# Power_Management.net
KiCad netlist of a schematic drawn in Altium Designer
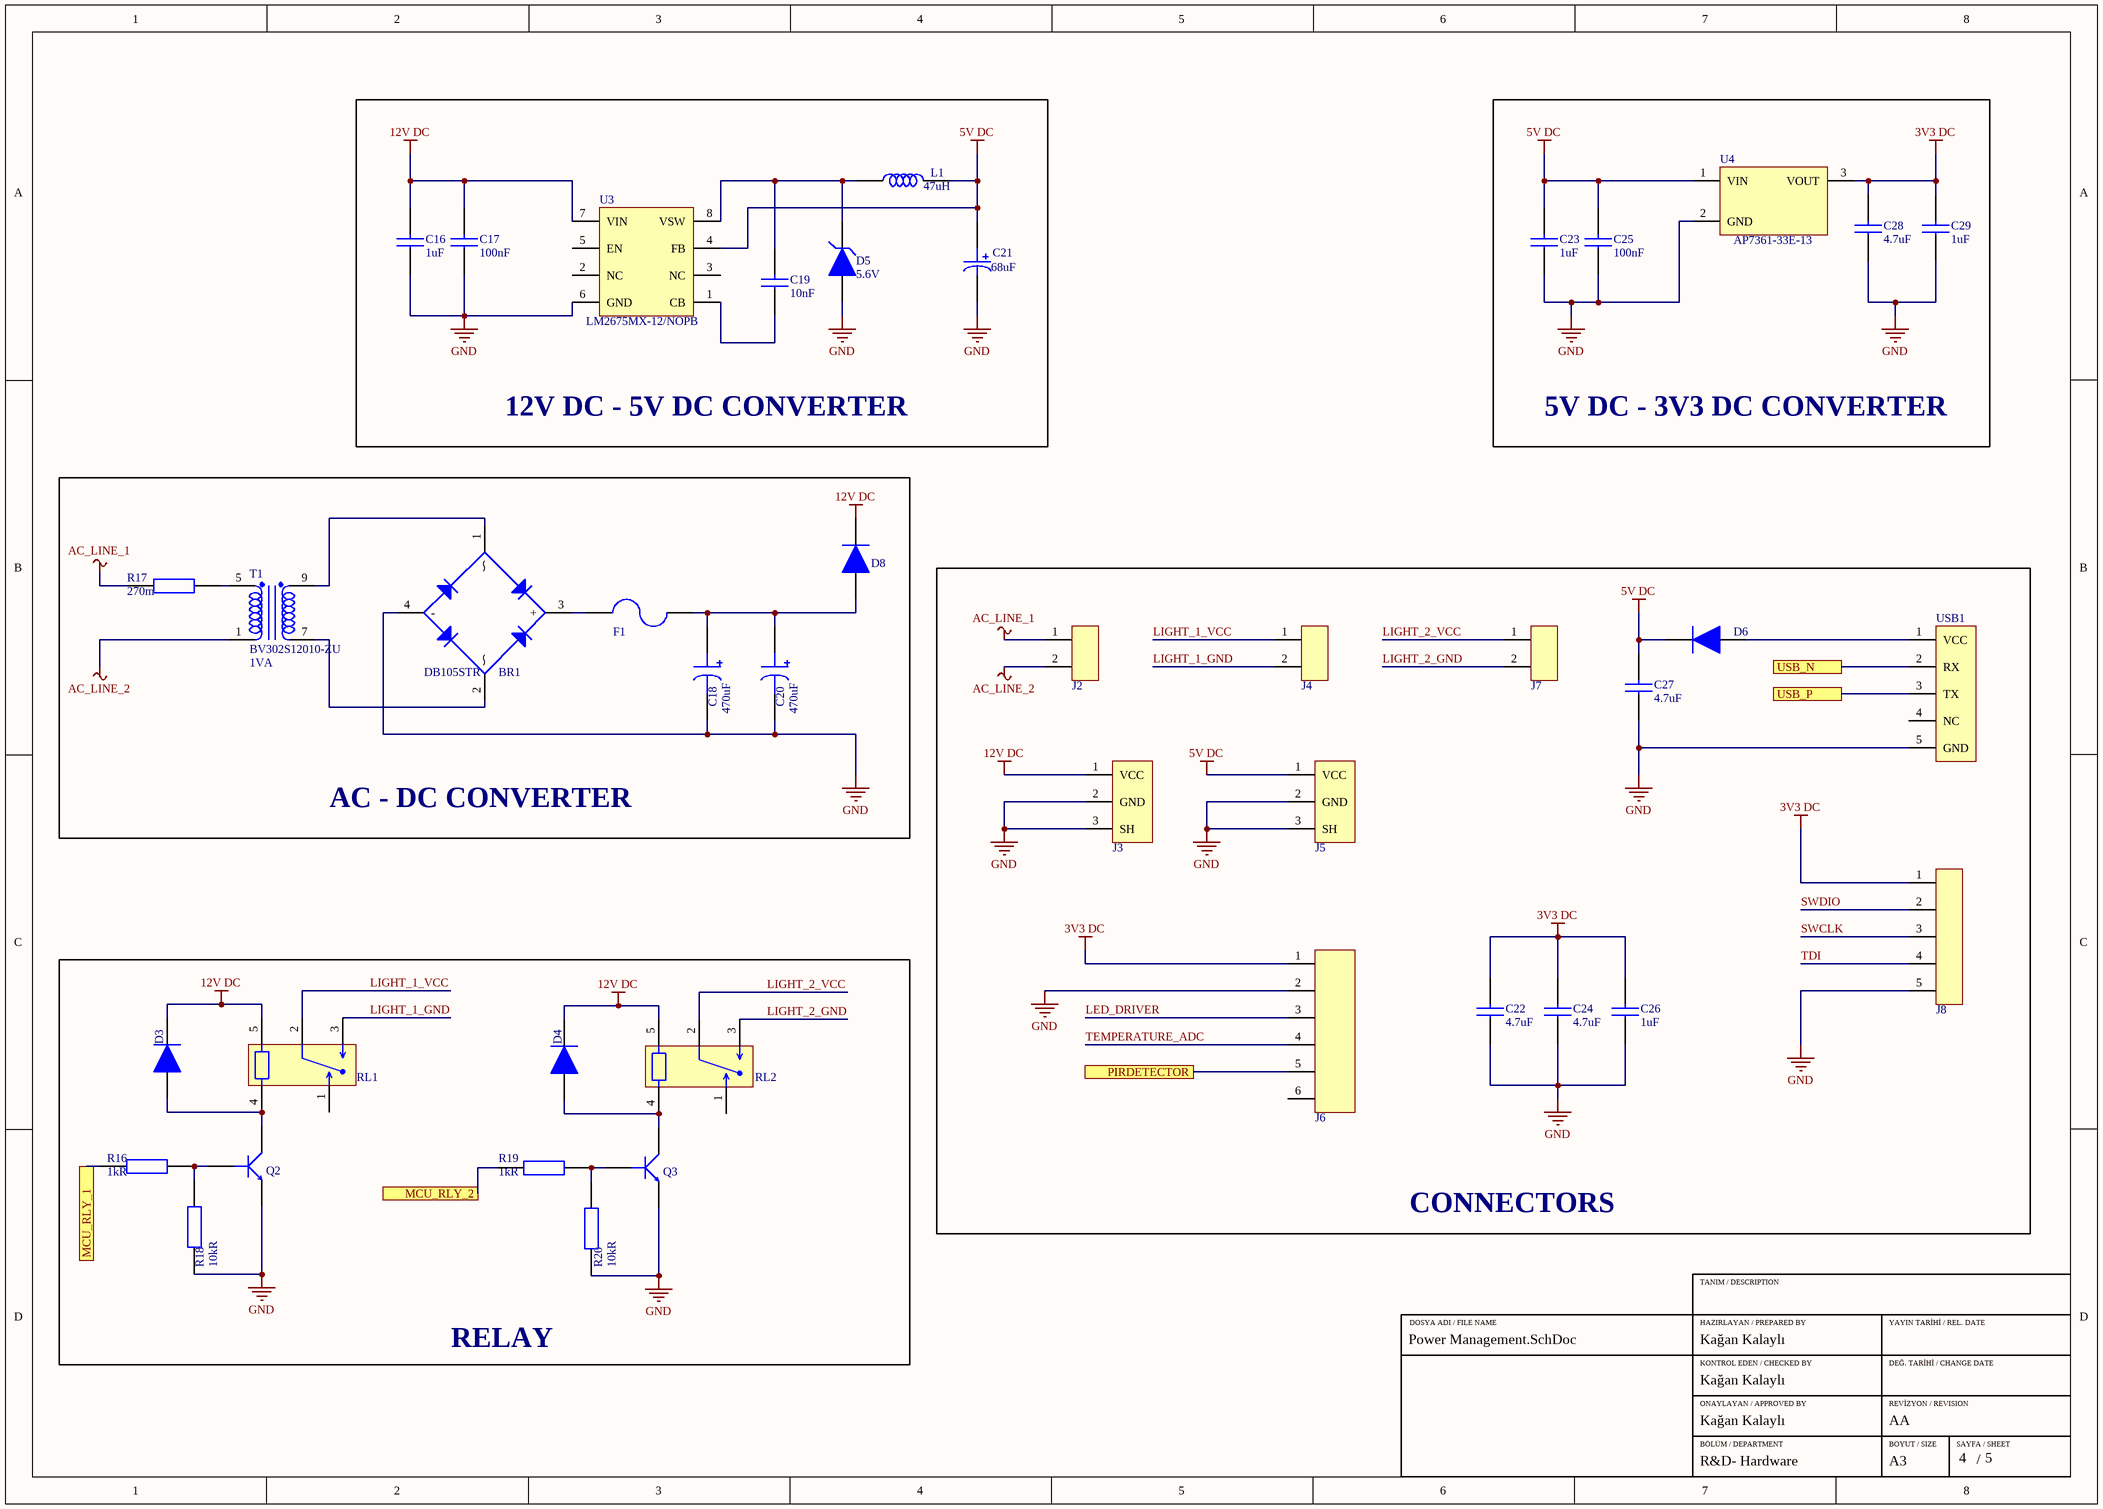
[diagram p0: Power Management.SchDoc]

(export (version "E")
  (design (tool "Eeschema 10.0.6"))
  (components
    (comp (ref "BR1")
      (value "DB105STR")
      (footprint "DB105STR")
      (description "Bridge Rect 1PHASE 600V 1A Db-s")
      (fields
        (field (name "MANUFACTURER") "Sangdest Microelectronics")
        (field (name "MANUFACTURER PART NUMBER") "DB105STR")
        (field (name "DESIGNED BY") "Kağan")
      )
      (libsource (lib "Udemy_Library") (part "DB105STR"))
    )
    (comp (ref "C16")
      (value "CL21B105KBFNNNE")
      (footprint "CAP_0805")
      (description "CAP CER 1uF %10 0805")
      (fields
        (field (name "MANUFACTURER") "Samsung")
        (field (name "TOLERANCE") "10%")
        (field (name "CAPACITANCE") "1uF")
        (field (name "DESIGNED BY") "Kağan")
      )
      (libsource (lib "Udemy_Library") (part "CAP CER 1uF 0805"))
    )
    (comp (ref "C17")
      (value "CL21B104KBCNNNC")
      (footprint "CAP_0805")
      (description "CAP CER 100nF %10 0805")
      (fields
        (field (name "MANUFACTURER") "Samsung")
        (field (name "TOLERANCE") "10%")
        (field (name "CAPACITANCE") "100nF")
        (field (name "DESIGNED BY") "Kağan")
      )
      (libsource (lib "Udemy_Library") (part "CAP CER 100nF 0805"))
    )
    (comp (ref "C18")
      (value "CAP ESH477M050AH4AA")
      (footprint "CAP_RADIAL_D10_P5 - duplicate")
      (description "Cap, 470UF, 50V, Alu Elec, Radial")
      (fields
        (field (name "MANUFACTURER") "KEMET")
        (field (name "MANUFACTURER PART NUMBER") "ESH477M050AH4AA")
        (field (name "CAPACITANCE") "470uF")
        (field (name "DESIGNED BY") "Kağan")
      )
      (libsource (lib "Udemy_Library") (part "CAP ESH477M050AH4AA"))
    )
    (comp (ref "C19")
      (value "0603B103K160CT")
      (footprint "CAP_0603")
      (description "CAP CER 10nF %10 0603")
      (fields
        (field (name "MANUFACTURER") "Walsin Technologies")
        (field (name "TOLERANCE") "10%")
        (field (name "CAPACITANCE") "10nF")
        (field (name "DESIGNED BY") "Kağan")
      )
      (libsource (lib "Udemy_Library") (part "CAP CER 10nF 0603"))
    )
    (comp (ref "C20")
      (value "CAP ESH477M050AH4AA")
      (footprint "CAP_RADIAL_D10_P5 - duplicate")
      (description "Cap, 470UF, 50V, Alu Elec, Radial")
      (fields
        (field (name "MANUFACTURER") "KEMET")
        (field (name "MANUFACTURER PART NUMBER") "ESH477M050AH4AA")
        (field (name "CAPACITANCE") "470uF")
        (field (name "DESIGNED BY") "Kağan")
      )
      (libsource (lib "Udemy_Library") (part "CAP ESH477M050AH4AA"))
    )
    (comp (ref "C21")
      (value "EEV686M035A9HAA")
      (footprint "CAP_EEVseries")
      (description "Cap Aluminum Lytic 68uF 35V 20% (6.3 X 7.7mm) SMD 280mA 2000h 105C T/R")
      (fields
        (field (name "MANUFACTURER") "KEMET")
        (field (name "TOLERANCE") "20%")
        (field (name "CAPACITANCE") "68uF")
        (field (name "DESIGNED BY") "Kağan")
      )
      (libsource (lib "Udemy_Library") (part "CAP ALU 68uF"))
    )
    (comp (ref "C22")
      (value "CL21A475KAQNNNE")
      (footprint "CAP_0805")
      (description "CAP CER 4.7uF %10 0805")
      (fields
        (field (name "MANUFACTURER") "Samsung")
        (field (name "TOLERANCE") "10%")
        (field (name "CAPACITANCE") "4.7uF")
        (field (name "DESIGNED BY") "Kağan")
      )
      (libsource (lib "Udemy_Library") (part "CAP CER 4.7uF 0805"))
    )
    (comp (ref "C23")
      (value "CL21B105KBFNNNE")
      (footprint "CAP_0805")
      (description "CAP CER 1uF %10 0805")
      (fields
        (field (name "MANUFACTURER") "Samsung")
        (field (name "TOLERANCE") "10%")
        (field (name "CAPACITANCE") "1uF")
        (field (name "DESIGNED BY") "Kağan")
      )
      (libsource (lib "Udemy_Library") (part "CAP CER 1uF 0805"))
    )
    (comp (ref "C24")
      (value "CL21A475KAQNNNE")
      (footprint "CAP_0805")
      (description "CAP CER 4.7uF %10 0805")
      (fields
        (field (name "MANUFACTURER") "Samsung")
        (field (name "TOLERANCE") "10%")
        (field (name "CAPACITANCE") "4.7uF")
        (field (name "DESIGNED BY") "Kağan")
      )
      (libsource (lib "Udemy_Library") (part "CAP CER 4.7uF 0805"))
    )
    (comp (ref "C25")
      (value "C0603C104K5RACTU")
      (footprint "CAP_0603")
      (description "CAP CER 100nF %10 0603 SMD")
      (fields
        (field (name "MANUFACTURER") "KEMET")
        (field (name "TOLERANCE") "10%")
        (field (name "CAPACITANCE") "100nF")
        (field (name "DESIGNED BY") "Kağan")
      )
      (libsource (lib "Udemy_Library") (part "CAP CER 100nF 0603_1"))
    )
    (comp (ref "C26")
      (value "CL21B105KBFNNNE")
      (footprint "CAP_0805")
      (description "CAP CER 1uF %10 0805")
      (fields
        (field (name "MANUFACTURER") "Samsung")
        (field (name "TOLERANCE") "10%")
        (field (name "CAPACITANCE") "1uF")
        (field (name "DESIGNED BY") "Kağan")
      )
      (libsource (lib "Udemy_Library") (part "CAP CER 1uF 0805"))
    )
    (comp (ref "C27")
      (value "CL21A475KAQNNNE")
      (footprint "CAP_0805")
      (description "CAP CER 4.7uF %10 0805")
      (fields
        (field (name "MANUFACTURER") "Samsung")
        (field (name "TOLERANCE") "10%")
        (field (name "CAPACITANCE") "4.7uF")
        (field (name "DESIGNED BY") "Kağan")
      )
      (libsource (lib "Udemy_Library") (part "CAP CER 4.7uF 0805"))
    )
    (comp (ref "C28")
      (value "CL21A475KAQNNNE")
      (footprint "CAP_0805")
      (description "CAP CER 4.7uF %10 0805")
      (fields
        (field (name "MANUFACTURER") "Samsung")
        (field (name "TOLERANCE") "10%")
        (field (name "CAPACITANCE") "4.7uF")
        (field (name "DESIGNED BY") "Kağan")
      )
      (libsource (lib "Udemy_Library") (part "CAP CER 4.7uF 0805"))
    )
    (comp (ref "C29")
      (value "CL21B105KBFNNNE")
      (footprint "CAP_0805")
      (description "CAP CER 1uF %10 0805")
      (fields
        (field (name "MANUFACTURER") "Samsung")
        (field (name "TOLERANCE") "10%")
        (field (name "CAPACITANCE") "1uF")
        (field (name "DESIGNED BY") "Kağan")
      )
      (libsource (lib "Udemy_Library") (part "CAP CER 1uF 0805"))
    )
    (comp (ref "D3")
      (value "1N4148WS")
      (footprint "SOD323F")
      (description "Diode, Single, 75 V, 150 mA, 1 V, 4 ns")
      (fields
        (field (name "MANUFACTURER") "ON Semiconductor / Fairchild")
        (field (name "DESIGNED BY") "Kağan")
      )
      (libsource (lib "Udemy_Library") (part "1N4148WS"))
    )
    (comp (ref "D4")
      (value "1N4148WS")
      (footprint "SOD323F")
      (description "Diode, Single, 75 V, 150 mA, 1 V, 4 ns")
      (fields
        (field (name "MANUFACTURER") "ON Semiconductor / Fairchild")
        (field (name "DESIGNED BY") "Kağan")
      )
      (libsource (lib "Udemy_Library") (part "1N4148WS"))
    )
    (comp (ref "D5")
      (value "1SMB5919BT3G")
      (footprint "SMB")
      (description "Diode Zener Single 5.6V 5% 3W 2-Pin SMB T/R")
      (fields
        (field (name "MANUFACTURER") "ON Semiconductor")
        (field (name "TOLERANCE") "5%")
        (field (name "WORKING VOLTAGE") "5.6V")
        (field (name "DESIGNED BY") "Kağan")
      )
      (libsource (lib "Udemy_Library") (part "1SMB5919BT3G"))
    )
    (comp (ref "D6")
      (value "1N4148WS")
      (footprint "SOD323F")
      (description "Diode, Single, 75 V, 150 mA, 1 V, 4 ns")
      (fields
        (field (name "MANUFACTURER") "ON Semiconductor / Fairchild")
        (field (name "DESIGNED BY") "Kağan")
      )
      (libsource (lib "Udemy_Library") (part "1N4148WS"))
    )
    (comp (ref "D8")
      (value "1N4148WS")
      (footprint "SOD323F")
      (description "Diode, Single, 75 V, 150 mA, 1 V, 4 ns")
      (fields
        (field (name "MANUFACTURER") "ON Semiconductor / Fairchild")
        (field (name "DESIGNED BY") "Kağan")
      )
      (libsource (lib "Udemy_Library") (part "1N4148WS"))
    )
    (comp (ref "F1")
      (value "3413.0216.22")
      (footprint "FUSE 3413.0216.22")
      (description "Fuse Chip Fast Acting 1A 32V SMD Solder Pad 1206 Glass T/R VDE/cULus")
      (fields (field (name "MANUFACTURER") "Schurter") (field (name "DESIGNED BY") "Kağan"))
      (libsource (lib "Udemy_Library") (part "FUSE 3413.0216.22"))
    )
    (comp (ref "J2")
      (value "TBP01R1-508-02BE")
      (footprint "TBP01R1-508")
      (description "Conn Shrouded Header HDR 2 POS 5.08mm Solder RA Side Entry Thru-Hole Bag")
      (fields (field (name "MANUFACTURER") "CUI") (field (name "DESIGNED BY") "Kağan"))
      (libsource (lib "Udemy_Library") (part "TBP01R1-508-02BE"))
    )
    (comp (ref "J3")
      (value "PJ-037AH-SMT-TR")
      (footprint "JACK")
      (description "DC Power Connectors Power Jacks")
      (fields (field (name "MANUFACTURER") "CUI") (field (name "DESIGNED BY") "Kağan"))
      (libsource (lib "Udemy_Library") (part "PJ-037AH-SMT-TR"))
    )
    (comp (ref "J4")
      (value "TBP01R1-508-02BE")
      (footprint "TBP01R1-508")
      (description "Conn Shrouded Header HDR 2 POS 5.08mm Solder RA Side Entry Thru-Hole Bag")
      (fields (field (name "MANUFACTURER") "CUI") (field (name "DESIGNED BY") "Kağan"))
      (libsource (lib "Udemy_Library") (part "TBP01R1-508-02BE"))
    )
    (comp (ref "J5")
      (value "PJ-037AH-SMT-TR")
      (footprint "JACK")
      (description "DC Power Connectors Power Jacks")
      (fields (field (name "MANUFACTURER") "CUI") (field (name "DESIGNED BY") "Kağan"))
      (libsource (lib "Udemy_Library") (part "PJ-037AH-SMT-TR"))
    )
    (comp (ref "J6")
      (value "64800611622")
      (footprint "64800611622")
      (description "1.50mm 6PIN Connector")
      (fields (field (name "MANUFACTURER") "Wurth Electronics") (field (name "DESIGNED BY") "Kağan"))
      (libsource (lib "Udemy_Library") (part "64800611622_conn_6pin"))
    )
    (comp (ref "J7")
      (value "TBP01R1-508-02BE")
      (footprint "TBP01R1-508")
      (description "Conn Shrouded Header HDR 2 POS 5.08mm Solder RA Side Entry Thru-Hole Bag")
      (fields (field (name "MANUFACTURER") "CUI") (field (name "DESIGNED BY") "Kağan"))
      (libsource (lib "Udemy_Library") (part "TBP01R1-508-02BE"))
    )
    (comp (ref "J8")
      (value "SMH-105-02-L-S")
      (footprint "PINHEADER1X5_RA")
      (description ".100 C.L. HORIZONTAL SMT SOCKET")
      (fields (field (name "MANUFACTURER") "Samtec") (field (name "DESIGNED BY") "Kağan"))
      (libsource (lib "Udemy_Library") (part "SMH-105-02-L-S"))
    )
    (comp (ref "L1")
      (value "78438335470")
      (footprint "IND_1212")
      (description "FIXED IND 47UH 390MA 2.3 OHM SMD")
      (fields
        (field (name "MANUFACTURER") "Wurth Electronics")
        (field (name "TOLERANCE") "30%")
        (field (name "INDUCTANCE") "47uH")
        (field (name "DESIGNED BY") "Kağan")
      )
      (libsource (lib "Udemy_Library") (part "IND 47uH"))
    )
    (comp (ref "Q2")
      (value "MMBT3904-7-F")
      (footprint "SOT-23F")
      (description "Transistor General Purpose BJT NPN 40 Volt 0.2A Automotive 3-Pin SOT-23")
      (fields (field (name "MANUFACTURER") "Diodes Zetex") (field (name "DESIGNED BY") "Kağan"))
      (libsource (lib "Udemy_Library") (part "MMBT3904-7-F"))
    )
    (comp (ref "Q3")
      (value "MMBT3904-7-F")
      (footprint "SOT-23F")
      (description "Transistor General Purpose BJT NPN 40 Volt 0.2A Automotive 3-Pin SOT-23")
      (fields (field (name "MANUFACTURER") "Diodes Zetex") (field (name "DESIGNED BY") "Kağan"))
      (libsource (lib "Udemy_Library") (part "MMBT3904-7-F"))
    )
    (comp (ref "R16")
      (value "RC0603FR-0710KL")
      (footprint "RES_0603")
      (description "RES 1K %1 OHM 0603 SMD")
      (fields
        (field (name "MANUFACTURER") "Yageo")
        (field (name "MANUFACTURER PART NUMBER") "RC0603JR-071KL")
        (field (name "RESISTANCE") "1kR")
        (field (name "DESIGNED BY") "Kağan")
      )
      (libsource (lib "Udemy_Library") (part "RES 1K OHM 0603"))
    )
    (comp (ref "R17")
      (value "5WD27")
      (footprint "RES_AXIAL_W")
      (description "Resistor 5 Watt Cermet Wirewound Flameproof .27 Ohm 5% Axial Lead")
      (fields
        (field (name "MANUFACTURER") "NTE Electronics")
        (field (name "TOLERANCE") "5%")
        (field (name "RESISTANCE") "270m")
        (field (name "DESIGNED BY") "Kağan")
      )
      (libsource (lib "Udemy_Library") (part "5WD27_1"))
    )
    (comp (ref "R18")
      (value "RC0603FR-0710KL")
      (footprint "RES_0603")
      (description "RES 10K %1 OHM 0603 SMD")
      (fields
        (field (name "MANUFACTURER") "Yageo")
        (field (name "TOLERANCE") "1%")
        (field (name "RESISTANCE") "10kR")
        (field (name "DESIGNED BY") "Kağan")
      )
      (libsource (lib "Udemy_Library") (part "RES 10K OHM 0603"))
    )
    (comp (ref "R19")
      (value "RC0603FR-0710KL")
      (footprint "RES_0603")
      (description "RES 1K %1 OHM 0603 SMD")
      (fields
        (field (name "MANUFACTURER") "Yageo")
        (field (name "MANUFACTURER PART NUMBER") "RC0603JR-071KL")
        (field (name "RESISTANCE") "1kR")
        (field (name "DESIGNED BY") "Kağan")
      )
      (libsource (lib "Udemy_Library") (part "RES 1K OHM 0603"))
    )
    (comp (ref "R20")
      (value "RC0603FR-0710KL")
      (footprint "RES_0603")
      (description "RES 10K %1 OHM 0603 SMD")
      (fields
        (field (name "MANUFACTURER") "Yageo")
        (field (name "TOLERANCE") "1%")
        (field (name "RESISTANCE") "10kR")
        (field (name "DESIGNED BY") "Kağan")
      )
      (libsource (lib "Udemy_Library") (part "RES 10K OHM 0603"))
    )
    (comp (ref "RL1")
      (value "ALQ112")
      (footprint "ALQ112")
      (description "PANASONIC - ALQ112 - POWER RELAY, SPDT, 12VDC, 10A, THD")
      (fields (field (name "MANUFACTURER") "Panasonic") (field (name "DESIGNED BY") "Kağan"))
      (libsource (lib "Udemy_Library") (part "ALQ112"))
    )
    (comp (ref "RL2")
      (value "ALQ112")
      (footprint "ALQ112")
      (description "PANASONIC - ALQ112 - POWER RELAY, SPDT, 12VDC, 10A, THD")
      (fields (field (name "MANUFACTURER") "Panasonic") (field (name "DESIGNED BY") "Kağan"))
      (libsource (lib "Udemy_Library") (part "ALQ112"))
    )
    (comp (ref "T1")
      (value "BV302S12010-ZU")
      (footprint "BV302S12010-ZU")
      (description "230-12 Transformer 1VA")
      (fields
        (field (name "MANUFACTURER") "Zettler Magnetics")
        (field (name "RATED POWER") "1VA")
        (field (name "DESIGNED BY") "Kağan")
      )
      (libsource (lib "Udemy_Library") (part "BV302S12010-ZU_1"))
    )
    (comp (ref "U3")
      (value "Buck Switching Regulator IC Positive Fixed 12V 1 Output 1A 8-SOIC (0.154\", 3.90mm Width)")
      (footprint "SOIC8")
      (description "SIMPLE SWITCHER® 6.5V to 40V, 1A Low Component Count Step-Down Regulator 8-SOIC -40 to 125")
      (fields
        (field (name "MANUFACTURER") "TI National Semiconductor")
        (field (name "MANUFACTURER PART NUMBER") "LM2675MX-12/NOPB")
        (field (name "DESIGNED BY") "Kağan")
      )
      (libsource (lib "Udemy_Library") (part "LM2675MX-12/NOPB"))
    )
    (comp (ref "U4")
      (value "AP7361-33E-13")
      (footprint "SOT223")
      (description "AP7361 Series 3.3 V 1 A Low SMT Dropout Fixed-Mode Regulator - SOT-223")
      (fields (field (name "MANUFACTURER") "Diodes") (field (name "DESIGNED BY") "Kağan"))
      (libsource (lib "Udemy_Library") (part "AP7361-33E-13"))
    )
    (comp (ref "USB1")
      (value "10118192-0001LF")
      (footprint "MICRO_B_USB")
      (description "CONN RCPT USB2.0 MICRO B SMD R/A")
      (fields (field (name "MANUFACTURER") "Amphenol FCI") (field (name "DESIGNED BY") "Kağan"))
      (libsource (lib "Udemy_Library") (part "Micro B USB Connector"))
    )
  )
  (nets
    (net (code "1") (name "/LED_DRIVER") (class "Default") (node (ref "J6") (pin "3") (pintype "power_in")))
    (net (code "2") (name "/LIGHT_1_GND") (class "Default")
      (node (ref "J4") (pin "2") (pinfunction "2_2") (pintype "power_in"))
      (node (ref "RL1") (pin "3") (pinfunction "3_3") (pintype "passive"))
    )
    (net (code "3") (name "/LIGHT_1_VCC") (class "Default")
      (node (ref "J4") (pin "1") (pinfunction "1_1") (pintype "power_in"))
      (node (ref "RL1") (pin "2") (pinfunction "2_2") (pintype "passive"))
    )
    (net (code "4") (name "/LIGHT_2_GND") (class "Default")
      (node (ref "J7") (pin "2") (pinfunction "2_2") (pintype "power_in"))
      (node (ref "RL2") (pin "3") (pinfunction "3_3") (pintype "passive"))
    )
    (net (code "5") (name "/LIGHT_2_VCC") (class "Default")
      (node (ref "J7") (pin "1") (pinfunction "1_1") (pintype "power_in"))
      (node (ref "RL2") (pin "2") (pinfunction "2_2") (pintype "passive"))
    )
    (net (code "6") (name "/MCU_RLY_1") (class "Default")
      (node (ref "R16") (pin "1") (pinfunction "1_1") (pintype "passive"))
    )
    (net (code "7") (name "/MCU_RLY_2") (class "Default")
      (node (ref "R19") (pin "1") (pinfunction "1_1") (pintype "passive"))
    )
    (net (code "8") (name "/PIRDETECTOR") (class "Default") (node (ref "J6") (pin "5") (pintype "power_in")))
    (net (code "9") (name "/SWCLK") (class "Default")
      (node (ref "J8") (pin "3") (pinfunction "3_3") (pintype "power_in"))
    )
    (net (code "10") (name "/SWDIO") (class "Default")
      (node (ref "J8") (pin "2") (pinfunction "2_2") (pintype "power_in"))
    )
    (net (code "11") (name "/TDI") (class "Default")
      (node (ref "J8") (pin "4") (pinfunction "4_4") (pintype "power_in"))
    )
    (net (code "12") (name "/TEMPERATURE_ADC") (class "Default")
      (node (ref "J6") (pin "4") (pintype "power_in"))
    )
    (net (code "13") (name "/USB_N") (class "Default")
      (node (ref "USB1") (pin "2") (pinfunction "RX_2") (pintype "power_in"))
    )
    (net (code "14") (name "/USB_P") (class "Default")
      (node (ref "USB1") (pin "3") (pinfunction "TX_3") (pintype "power_in"))
    )
    (net (code "15") (name "3V3 DC") (class "Default")
      (node (ref "C22") (pin "2") (pinfunction "2_2") (pintype "passive"))
      (node (ref "C24") (pin "2") (pinfunction "2_2") (pintype "passive"))
      (node (ref "C26") (pin "2") (pinfunction "2_2") (pintype "passive"))
      (node (ref "C28") (pin "2") (pinfunction "2_2") (pintype "passive"))
      (node (ref "C29") (pin "2") (pinfunction "2_2") (pintype "passive"))
      (node (ref "J6") (pin "1") (pintype "power_in"))
      (node (ref "J8") (pin "1") (pinfunction "1_1") (pintype "power_in"))
      (node (ref "U4") (pin "3") (pinfunction "VOUT_3") (pintype "passive"))
    )
    (net (code "16") (name "5V DC") (class "Default")
      (node (ref "C21") (pin "1") (pinfunction "1_1") (pintype "passive"))
      (node (ref "C23") (pin "2") (pinfunction "2_2") (pintype "passive"))
      (node (ref "C25") (pin "2") (pinfunction "2_2") (pintype "passive"))
      (node (ref "C27") (pin "2") (pinfunction "2_2") (pintype "passive"))
      (node (ref "D6") (pin "1") (pinfunction "1_1") (pintype "power_in"))
      (node (ref "J5") (pin "1") (pinfunction "VCC_1") (pintype "power_in"))
      (node (ref "L1") (pin "2") (pinfunction "2_2") (pintype "passive"))
      (node (ref "U3") (pin "4") (pinfunction "FB_4") (pintype "passive"))
      (node (ref "U4") (pin "1") (pinfunction "VIN_1") (pintype "passive"))
    )
    (net (code "17") (name "12V DC") (class "Default")
      (node (ref "C16") (pin "2") (pinfunction "2_2") (pintype "passive"))
      (node (ref "C17") (pin "2") (pinfunction "2_2") (pintype "passive"))
      (node (ref "D3") (pin "1") (pinfunction "1_1") (pintype "power_in"))
      (node (ref "D4") (pin "1") (pinfunction "1_1") (pintype "power_in"))
      (node (ref "D8") (pin "1") (pinfunction "1_1") (pintype "power_in"))
      (node (ref "J3") (pin "1") (pinfunction "VCC_1") (pintype "power_in"))
      (node (ref "RL1") (pin "5") (pinfunction "5_5") (pintype "passive"))
      (node (ref "RL2") (pin "5") (pinfunction "5_5") (pintype "passive"))
      (node (ref "U3") (pin "7") (pinfunction "VIN_7") (pintype "passive"))
    )
    (net (code "18") (name "AC_LINE_1") (class "Default")
      (node (ref "J2") (pin "1") (pinfunction "1_1") (pintype "power_in"))
      (node (ref "R17") (pin "1") (pinfunction "1_1") (pintype "passive"))
    )
    (net (code "19") (name "AC_LINE_2") (class "Default")
      (node (ref "J2") (pin "2") (pinfunction "2_2") (pintype "power_in"))
      (node (ref "T1") (pin "1") (pinfunction "1_1") (pintype "passive"))
    )
    (net (code "20") (name "GND") (class "Default")
      (node (ref "BR1") (pin "4") (pinfunction "-_4") (pintype "passive"))
      (node (ref "C16") (pin "1") (pinfunction "1_1") (pintype "passive"))
      (node (ref "C17") (pin "1") (pinfunction "1_1") (pintype "passive"))
      (node (ref "C18") (pin "2") (pintype "passive"))
      (node (ref "C20") (pin "2") (pintype "passive"))
      (node (ref "C21") (pin "2") (pinfunction "2_2") (pintype "passive"))
      (node (ref "C22") (pin "1") (pinfunction "1_1") (pintype "passive"))
      (node (ref "C23") (pin "1") (pinfunction "1_1") (pintype "passive"))
      (node (ref "C24") (pin "1") (pinfunction "1_1") (pintype "passive"))
      (node (ref "C25") (pin "1") (pinfunction "1_1") (pintype "passive"))
      (node (ref "C26") (pin "1") (pinfunction "1_1") (pintype "passive"))
      (node (ref "C27") (pin "1") (pinfunction "1_1") (pintype "passive"))
      (node (ref "C28") (pin "1") (pinfunction "1_1") (pintype "passive"))
      (node (ref "C29") (pin "1") (pinfunction "1_1") (pintype "passive"))
      (node (ref "D5") (pin "A") (pinfunction "A_A") (pintype "passive"))
      (node (ref "J3") (pin "2") (pinfunction "GND_2") (pintype "power_in"))
      (node (ref "J3") (pin "3") (pinfunction "SH_3") (pintype "power_in"))
      (node (ref "J5") (pin "2") (pinfunction "GND_2") (pintype "power_in"))
      (node (ref "J5") (pin "3") (pinfunction "SH_3") (pintype "power_in"))
      (node (ref "J6") (pin "2") (pintype "power_in"))
      (node (ref "J8") (pin "5") (pinfunction "5_5") (pintype "power_in"))
      (node (ref "Q2") (pin "2") (pinfunction "E_2") (pintype "power_in"))
      (node (ref "Q3") (pin "2") (pinfunction "E_2") (pintype "power_in"))
      (node (ref "R18") (pin "1") (pinfunction "1_1") (pintype "passive"))
      (node (ref "R20") (pin "1") (pinfunction "1_1") (pintype "passive"))
      (node (ref "U3") (pin "6") (pinfunction "GND_6") (pintype "passive"))
      (node (ref "U4") (pin "2") (pinfunction "GND_2") (pintype "passive"))
      (node (ref "USB1") (pin "5") (pinfunction "GND_5") (pintype "power_in"))
    )
    (net (code "21") (name "Net-(BR1-+)") (class "Default")
      (node (ref "BR1") (pin "3") (pinfunction "+_3") (pintype "passive"))
      (node (ref "F1") (pin "1") (pintype "passive"))
    )
    (net (code "22") (name "Net-(BR1-〜-Pad1)") (class "Default")
      (node (ref "BR1") (pin "1") (pinfunction "〜_1") (pintype "passive"))
      (node (ref "T1") (pin "9") (pinfunction "9_9") (pintype "passive"))
    )
    (net (code "23") (name "Net-(BR1-〜-Pad2)") (class "Default")
      (node (ref "BR1") (pin "2") (pinfunction "〜_2") (pintype "passive"))
      (node (ref "T1") (pin "7") (pinfunction "7_7") (pintype "passive"))
    )
    (net (code "24") (name "Net-(C18-Pad1)") (class "Default")
      (node (ref "C18") (pin "1") (pintype "passive"))
      (node (ref "C20") (pin "1") (pintype "passive"))
      (node (ref "D8") (pin "2") (pinfunction "2_2") (pintype "power_in"))
      (node (ref "F1") (pin "2") (pintype "passive"))
    )
    (net (code "25") (name "Net-(Q2-B)") (class "Default")
      (node (ref "Q2") (pin "1") (pinfunction "B_1") (pintype "power_in"))
      (node (ref "R16") (pin "2") (pinfunction "2_2") (pintype "passive"))
      (node (ref "R18") (pin "2") (pinfunction "2_2") (pintype "passive"))
    )
    (net (code "26") (name "Net-(Q2-C)") (class "Default")
      (node (ref "D3") (pin "2") (pinfunction "2_2") (pintype "power_in"))
      (node (ref "Q2") (pin "3") (pinfunction "C_3") (pintype "power_in"))
      (node (ref "RL1") (pin "4") (pinfunction "4_4") (pintype "passive"))
    )
    (net (code "27") (name "Net-(Q3-B)") (class "Default")
      (node (ref "Q3") (pin "1") (pinfunction "B_1") (pintype "power_in"))
      (node (ref "R19") (pin "2") (pinfunction "2_2") (pintype "passive"))
      (node (ref "R20") (pin "2") (pinfunction "2_2") (pintype "passive"))
    )
    (net (code "28") (name "Net-(Q3-C)") (class "Default")
      (node (ref "D4") (pin "2") (pinfunction "2_2") (pintype "power_in"))
      (node (ref "Q3") (pin "3") (pinfunction "C_3") (pintype "power_in"))
      (node (ref "RL2") (pin "4") (pinfunction "4_4") (pintype "passive"))
    )
    (net (code "29") (name "Net-(R17-Pad2)") (class "Default")
      (node (ref "R17") (pin "2") (pinfunction "2_2") (pintype "passive"))
      (node (ref "T1") (pin "5") (pinfunction "5_5") (pintype "passive"))
    )
    (net (code "30") (name "Net-(U3-CB)") (class "Default")
      (node (ref "C19") (pin "1") (pinfunction "1_1") (pintype "passive"))
      (node (ref "U3") (pin "1") (pinfunction "CB_1") (pintype "passive"))
    )
    (net (code "31") (name "Net-(U3-VSW)") (class "Default")
      (node (ref "C19") (pin "2") (pinfunction "2_2") (pintype "passive"))
      (node (ref "D5") (pin "C") (pinfunction "C_C") (pintype "passive"))
      (node (ref "L1") (pin "1") (pinfunction "1_1") (pintype "passive"))
      (node (ref "U3") (pin "8") (pinfunction "VSW_8") (pintype "passive"))
    )
    (net (code "32") (name "Net-(USB1-VCC)") (class "Default")
      (node (ref "D6") (pin "2") (pinfunction "2_2") (pintype "power_in"))
      (node (ref "USB1") (pin "1") (pinfunction "VCC_1") (pintype "power_in"))
    )
    (net (code "33") (name "unconnected-(J6-Pad6)") (class "Default")
      (node (ref "J6") (pin "6") (pintype "power_in"))
    )
    (net (code "34") (name "unconnected-(RL1-Pad1)") (class "Default")
      (node (ref "RL1") (pin "1") (pinfunction "1_1") (pintype "passive"))
    )
    (net (code "35") (name "unconnected-(RL2-Pad1)") (class "Default")
      (node (ref "RL2") (pin "1") (pinfunction "1_1") (pintype "passive"))
    )
    (net (code "36") (name "unconnected-(U3-EN-Pad5)") (class "Default")
      (node (ref "U3") (pin "5") (pinfunction "EN_5") (pintype "passive"))
    )
    (net (code "37") (name "unconnected-(U3-NC-Pad2)") (class "Default")
      (node (ref "U3") (pin "2") (pinfunction "NC_2") (pintype "passive"))
    )
    (net (code "38") (name "unconnected-(U3-NC-Pad3)") (class "Default")
      (node (ref "U3") (pin "3") (pinfunction "NC_3") (pintype "passive"))
    )
    (net (code "39") (name "unconnected-(USB1-NC-Pad4)") (class "Default")
      (node (ref "USB1") (pin "4") (pinfunction "NC_4") (pintype "power_in"))
    )
  )
)
